# Temp.net
KiCad netlist of a schematic drawn in EAGLE
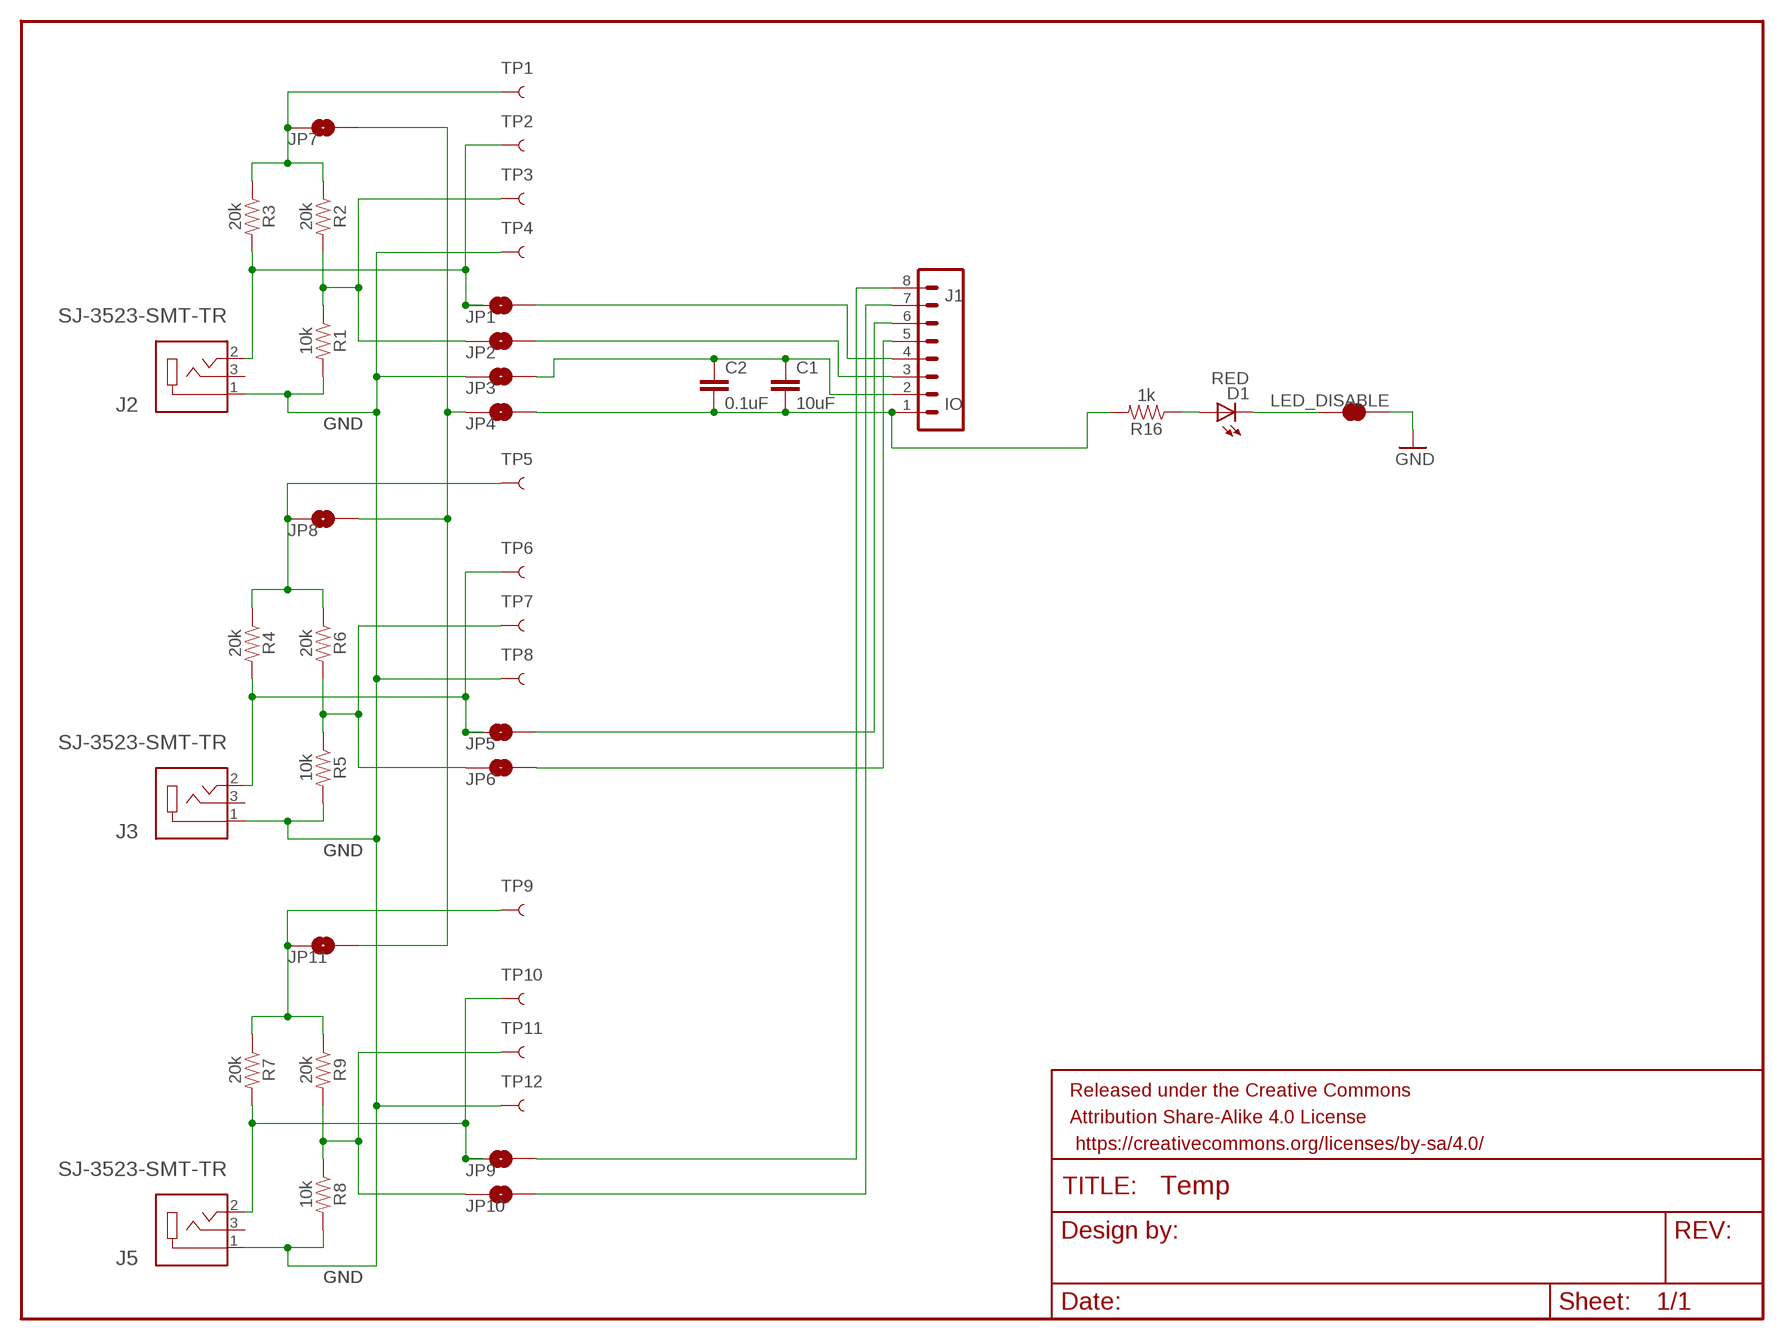
[diagram p0: schematic, sheet 1]

(export (version "E")
  (design (tool "Eeschema 10.0.6"))
  (components
    (comp (ref "C1")
      (value "10uF")
      (footprint "eagle-import:0603")
      (libsource (lib "eagle-import") (part "10UF-0603-6.3V-20%"))
    )
    (comp (ref "C2")
      (value "0.1uF")
      (footprint "eagle-import:0603")
      (libsource (lib "eagle-import") (part "0.1UF-0603-25V-(+80/-20%)"))
    )
    (comp (ref "D1")
      (value "RED")
      (footprint "eagle-import:LED-0603")
      (libsource (lib "eagle-import") (part "LED-RED0603"))
    )
    (comp (ref "FRAME1")
      (value "FRAME-LETTERNO_PACKAGE")
      (footprint "eagle-import:DUMMY")
      (fields (field (name "DESIGNER") "Nobody"))
      (libsource (lib "eagle-import") (part "FRAME-LETTERNO_PACKAGE"))
    )
    (comp (ref "J1")
      (value "IO")
      (footprint "eagle-import:1X08")
      (libsource (lib "eagle-import") (part "CONN_08{dblquote}"))
    )
    (comp (ref "J2")
      (value "SJ-3523-SMT-TR")
      (footprint "eagle-import:CUI_SJ-3523-SMT-TR")
      (fields (field (name "MF") "CUI Devices"))
      (libsource (lib "eagle-import") (part "SJ-3523-SMT-TR"))
    )
    (comp (ref "J3")
      (value "SJ-3523-SMT-TR")
      (footprint "eagle-import:CUI_SJ-3523-SMT-TR")
      (fields (field (name "MF") "CUI Devices"))
      (libsource (lib "eagle-import") (part "SJ-3523-SMT-TR"))
    )
    (comp (ref "J5")
      (value "SJ-3523-SMT-TR")
      (footprint "eagle-import:CUI_SJ-3523-SMT-TR")
      (fields (field (name "MF") "CUI Devices"))
      (libsource (lib "eagle-import") (part "SJ-3523-SMT-TR"))
    )
    (comp (ref "JP1")
      (value "JUMPER-SMT_2_NO_NO-SILK")
      (footprint "eagle-import:SMT-JUMPER_2_NO_NO-SILK")
      (libsource (lib "eagle-import") (part "JUMPER-SMT_2_NO_NO-SILK"))
    )
    (comp (ref "JP2")
      (value "JUMPER-SMT_2_NO_NO-SILK")
      (footprint "eagle-import:SMT-JUMPER_2_NO_NO-SILK")
      (libsource (lib "eagle-import") (part "JUMPER-SMT_2_NO_NO-SILK"))
    )
    (comp (ref "JP3")
      (value "JUMPER-SMT_2_NO_NO-SILK")
      (footprint "eagle-import:SMT-JUMPER_2_NO_NO-SILK")
      (libsource (lib "eagle-import") (part "JUMPER-SMT_2_NO_NO-SILK"))
    )
    (comp (ref "JP4")
      (value "JUMPER-SMT_2_NO_NO-SILK")
      (footprint "eagle-import:SMT-JUMPER_2_NO_NO-SILK")
      (libsource (lib "eagle-import") (part "JUMPER-SMT_2_NO_NO-SILK"))
    )
    (comp (ref "JP5")
      (value "JUMPER-SMT_2_NO_NO-SILK")
      (footprint "eagle-import:SMT-JUMPER_2_NO_NO-SILK")
      (libsource (lib "eagle-import") (part "JUMPER-SMT_2_NO_NO-SILK"))
    )
    (comp (ref "JP6")
      (value "JUMPER-SMT_2_NO_NO-SILK")
      (footprint "eagle-import:SMT-JUMPER_2_NO_NO-SILK")
      (libsource (lib "eagle-import") (part "JUMPER-SMT_2_NO_NO-SILK"))
    )
    (comp (ref "JP7")
      (value "JUMPER-SMT_2_NO_NO-SILK")
      (footprint "eagle-import:SMT-JUMPER_2_NO_NO-SILK")
      (libsource (lib "eagle-import") (part "JUMPER-SMT_2_NO_NO-SILK"))
    )
    (comp (ref "JP8")
      (value "JUMPER-SMT_2_NO_NO-SILK")
      (footprint "eagle-import:SMT-JUMPER_2_NO_NO-SILK")
      (libsource (lib "eagle-import") (part "JUMPER-SMT_2_NO_NO-SILK"))
    )
    (comp (ref "JP9")
      (value "JUMPER-SMT_2_NO_NO-SILK")
      (footprint "eagle-import:SMT-JUMPER_2_NO_NO-SILK")
      (libsource (lib "eagle-import") (part "JUMPER-SMT_2_NO_NO-SILK"))
    )
    (comp (ref "JP10")
      (value "JUMPER-SMT_2_NO_NO-SILK")
      (footprint "eagle-import:SMT-JUMPER_2_NO_NO-SILK")
      (libsource (lib "eagle-import") (part "JUMPER-SMT_2_NO_NO-SILK"))
    )
    (comp (ref "JP11")
      (value "JUMPER-SMT_2_NO_NO-SILK")
      (footprint "eagle-import:SMT-JUMPER_2_NO_NO-SILK")
      (libsource (lib "eagle-import") (part "JUMPER-SMT_2_NO_NO-SILK"))
    )
    (comp (ref "LED_DISABLE")
      (value "JUMPER-SMT_2_NC_TRACE_SILK")
      (footprint "eagle-import:SMT-JUMPER_2_NC_TRACE_SILK")
      (libsource (lib "eagle-import") (part "JUMPER-SMT_2_NC_TRACE_SILK"))
    )
    (comp (ref "R1")
      (value "10k")
      (footprint "eagle-import:0603")
      (libsource (lib "eagle-import") (part "10KOHM-0603-1/10W-1%"))
    )
    (comp (ref "R2")
      (value "20k")
      (footprint "eagle-import:0603")
      (libsource (lib "eagle-import") (part "20KOHM-0603-1/10W-1%"))
    )
    (comp (ref "R3")
      (value "20k")
      (footprint "eagle-import:0603")
      (libsource (lib "eagle-import") (part "20KOHM-0603-1/10W-1%"))
    )
    (comp (ref "R4")
      (value "20k")
      (footprint "eagle-import:0603")
      (libsource (lib "eagle-import") (part "20KOHM-0603-1/10W-1%"))
    )
    (comp (ref "R5")
      (value "10k")
      (footprint "eagle-import:0603")
      (libsource (lib "eagle-import") (part "10KOHM-0603-1/10W-1%"))
    )
    (comp (ref "R6")
      (value "20k")
      (footprint "eagle-import:0603")
      (libsource (lib "eagle-import") (part "20KOHM-0603-1/10W-1%"))
    )
    (comp (ref "R7")
      (value "20k")
      (footprint "eagle-import:0603")
      (libsource (lib "eagle-import") (part "20KOHM-0603-1/10W-1%"))
    )
    (comp (ref "R8")
      (value "10k")
      (footprint "eagle-import:0603")
      (libsource (lib "eagle-import") (part "10KOHM-0603-1/10W-1%"))
    )
    (comp (ref "R9")
      (value "20k")
      (footprint "eagle-import:0603")
      (libsource (lib "eagle-import") (part "20KOHM-0603-1/10W-1%"))
    )
    (comp (ref "R16")
      (value "1k")
      (footprint "eagle-import:0603")
      (libsource (lib "eagle-import") (part "1KOHM-0603-1/10W-1%"))
    )
    (comp (ref "TP1")
      (value "TEST-POINT3X5")
      (footprint "eagle-import:PAD.03X.05")
      (libsource (lib "eagle-import") (part "TEST-POINT3X5"))
    )
    (comp (ref "TP2")
      (value "TEST-POINT3X5")
      (footprint "eagle-import:PAD.03X.05")
      (libsource (lib "eagle-import") (part "TEST-POINT3X5"))
    )
    (comp (ref "TP3")
      (value "TEST-POINT3X5")
      (footprint "eagle-import:PAD.03X.05")
      (libsource (lib "eagle-import") (part "TEST-POINT3X5"))
    )
    (comp (ref "TP4")
      (value "TEST-POINT3X5")
      (footprint "eagle-import:PAD.03X.05")
      (libsource (lib "eagle-import") (part "TEST-POINT3X5"))
    )
    (comp (ref "TP5")
      (value "TEST-POINT3X5")
      (footprint "eagle-import:PAD.03X.05")
      (libsource (lib "eagle-import") (part "TEST-POINT3X5"))
    )
    (comp (ref "TP6")
      (value "TEST-POINT3X5")
      (footprint "eagle-import:PAD.03X.05")
      (libsource (lib "eagle-import") (part "TEST-POINT3X5"))
    )
    (comp (ref "TP7")
      (value "TEST-POINT3X5")
      (footprint "eagle-import:PAD.03X.05")
      (libsource (lib "eagle-import") (part "TEST-POINT3X5"))
    )
    (comp (ref "TP8")
      (value "TEST-POINT3X5")
      (footprint "eagle-import:PAD.03X.05")
      (libsource (lib "eagle-import") (part "TEST-POINT3X5"))
    )
    (comp (ref "TP9")
      (value "TEST-POINT3X5")
      (footprint "eagle-import:PAD.03X.05")
      (libsource (lib "eagle-import") (part "TEST-POINT3X5"))
    )
    (comp (ref "TP10")
      (value "TEST-POINT3X5")
      (footprint "eagle-import:PAD.03X.05")
      (libsource (lib "eagle-import") (part "TEST-POINT3X5"))
    )
    (comp (ref "TP11")
      (value "TEST-POINT3X5")
      (footprint "eagle-import:PAD.03X.05")
      (libsource (lib "eagle-import") (part "TEST-POINT3X5"))
    )
    (comp (ref "TP12")
      (value "TEST-POINT3X5")
      (footprint "eagle-import:PAD.03X.05")
      (libsource (lib "eagle-import") (part "TEST-POINT3X5"))
    )
  )
  (nets
    (net (code "1") (name "GND") (class "Default")
      (node (ref "J2") (pin "1") (pinfunction "1_1") (pintype "passive"))
      (node (ref "J3") (pin "1") (pinfunction "1_1") (pintype "passive"))
      (node (ref "J5") (pin "1") (pinfunction "1_1") (pintype "passive"))
      (node (ref "JP3") (pin "1") (pinfunction "1_1") (pintype "passive"))
      (node (ref "LED_DISABLE") (pin "1") (pinfunction "1_1") (pintype "passive"))
      (node (ref "R1") (pin "2") (pinfunction "2_2") (pintype "passive"))
      (node (ref "R5") (pin "2") (pinfunction "2_2") (pintype "passive"))
      (node (ref "R8") (pin "2") (pinfunction "2_2") (pintype "passive"))
      (node (ref "TP12") (pin "P$1") (pinfunction "1_P$1") (pintype "bidirectional"))
      (node (ref "TP4") (pin "P$1") (pinfunction "1_P$1") (pintype "bidirectional"))
      (node (ref "TP8") (pin "P$1") (pinfunction "1_P$1") (pintype "bidirectional"))
    )
    (net (code "2") (name "Net-(C1-Pad1)") (class "Default")
      (node (ref "C1") (pin "1") (pinfunction "1_1") (pintype "passive"))
      (node (ref "C2") (pin "1") (pinfunction "1_1") (pintype "passive"))
      (node (ref "J1") (pin "2") (pinfunction "2_2") (pintype "passive"))
      (node (ref "JP3") (pin "2") (pinfunction "2_2") (pintype "passive"))
    )
    (net (code "3") (name "Net-(C1-Pad2)") (class "Default")
      (node (ref "C1") (pin "2") (pinfunction "2_2") (pintype "passive"))
      (node (ref "C2") (pin "2") (pinfunction "2_2") (pintype "passive"))
      (node (ref "J1") (pin "1") (pinfunction "1_1") (pintype "passive"))
      (node (ref "JP4") (pin "2") (pinfunction "2_2") (pintype "passive"))
      (node (ref "R16") (pin "2") (pinfunction "2_2") (pintype "passive"))
    )
    (net (code "4") (name "Net-(D1-PadA)") (class "Default")
      (node (ref "D1") (pin "A") (pinfunction "A_A") (pintype "passive"))
      (node (ref "R16") (pin "1") (pinfunction "1_1") (pintype "passive"))
    )
    (net (code "5") (name "Net-(D1-PadC)") (class "Default")
      (node (ref "D1") (pin "C") (pinfunction "C_C") (pintype "passive"))
      (node (ref "LED_DISABLE") (pin "2") (pinfunction "2_2") (pintype "passive"))
    )
    (net (code "6") (name "Net-(J1-Pad3)") (class "Default")
      (node (ref "J1") (pin "3") (pinfunction "3_3") (pintype "passive"))
      (node (ref "JP2") (pin "2") (pinfunction "2_2") (pintype "passive"))
    )
    (net (code "7") (name "Net-(J1-Pad4)") (class "Default")
      (node (ref "J1") (pin "4") (pinfunction "4_4") (pintype "passive"))
      (node (ref "JP1") (pin "2") (pinfunction "2_2") (pintype "passive"))
    )
    (net (code "8") (name "Net-(J1-Pad5)") (class "Default")
      (node (ref "J1") (pin "5") (pinfunction "5_5") (pintype "passive"))
      (node (ref "JP6") (pin "2") (pinfunction "2_2") (pintype "passive"))
    )
    (net (code "9") (name "Net-(J1-Pad6)") (class "Default")
      (node (ref "J1") (pin "6") (pinfunction "6_6") (pintype "passive"))
      (node (ref "JP5") (pin "2") (pinfunction "2_2") (pintype "passive"))
    )
    (net (code "10") (name "Net-(J1-Pad7)") (class "Default")
      (node (ref "J1") (pin "7") (pinfunction "7_7") (pintype "passive"))
      (node (ref "JP10") (pin "2") (pinfunction "2_2") (pintype "passive"))
    )
    (net (code "11") (name "Net-(J1-Pad8)") (class "Default")
      (node (ref "J1") (pin "8") (pinfunction "8_8") (pintype "passive"))
      (node (ref "JP9") (pin "2") (pinfunction "2_2") (pintype "passive"))
    )
    (net (code "12") (name "Net-(JP11-Pad2)") (class "Default")
      (node (ref "JP11") (pin "2") (pinfunction "2_2") (pintype "passive"))
      (node (ref "JP4") (pin "1") (pinfunction "1_1") (pintype "passive"))
      (node (ref "JP7") (pin "2") (pinfunction "2_2") (pintype "passive"))
      (node (ref "JP8") (pin "2") (pinfunction "2_2") (pintype "passive"))
    )
    (net (code "13") (name "Net-(TP1-1)") (class "Default")
      (node (ref "JP7") (pin "1") (pinfunction "1_1") (pintype "passive"))
      (node (ref "R2") (pin "1") (pinfunction "1_1") (pintype "passive"))
      (node (ref "R3") (pin "1") (pinfunction "1_1") (pintype "passive"))
      (node (ref "TP1") (pin "P$1") (pinfunction "1_P$1") (pintype "bidirectional"))
    )
    (net (code "14") (name "Net-(TP2-1)") (class "Default")
      (node (ref "J2") (pin "2") (pinfunction "2_2") (pintype "passive"))
      (node (ref "JP1") (pin "1") (pinfunction "1_1") (pintype "passive"))
      (node (ref "R3") (pin "2") (pinfunction "2_2") (pintype "passive"))
      (node (ref "TP2") (pin "P$1") (pinfunction "1_P$1") (pintype "bidirectional"))
    )
    (net (code "15") (name "Net-(TP3-1)") (class "Default")
      (node (ref "JP2") (pin "1") (pinfunction "1_1") (pintype "passive"))
      (node (ref "R1") (pin "1") (pinfunction "1_1") (pintype "passive"))
      (node (ref "R2") (pin "2") (pinfunction "2_2") (pintype "passive"))
      (node (ref "TP3") (pin "P$1") (pinfunction "1_P$1") (pintype "bidirectional"))
    )
    (net (code "16") (name "Net-(TP5-1)") (class "Default")
      (node (ref "JP8") (pin "1") (pinfunction "1_1") (pintype "passive"))
      (node (ref "R4") (pin "1") (pinfunction "1_1") (pintype "passive"))
      (node (ref "R6") (pin "1") (pinfunction "1_1") (pintype "passive"))
      (node (ref "TP5") (pin "P$1") (pinfunction "1_P$1") (pintype "bidirectional"))
    )
    (net (code "17") (name "Net-(TP6-1)") (class "Default")
      (node (ref "J3") (pin "2") (pinfunction "2_2") (pintype "passive"))
      (node (ref "JP5") (pin "1") (pinfunction "1_1") (pintype "passive"))
      (node (ref "R4") (pin "2") (pinfunction "2_2") (pintype "passive"))
      (node (ref "TP6") (pin "P$1") (pinfunction "1_P$1") (pintype "bidirectional"))
    )
    (net (code "18") (name "Net-(TP7-1)") (class "Default")
      (node (ref "JP6") (pin "1") (pinfunction "1_1") (pintype "passive"))
      (node (ref "R5") (pin "1") (pinfunction "1_1") (pintype "passive"))
      (node (ref "R6") (pin "2") (pinfunction "2_2") (pintype "passive"))
      (node (ref "TP7") (pin "P$1") (pinfunction "1_P$1") (pintype "bidirectional"))
    )
    (net (code "19") (name "Net-(TP9-1)") (class "Default")
      (node (ref "JP11") (pin "1") (pinfunction "1_1") (pintype "passive"))
      (node (ref "R7") (pin "1") (pinfunction "1_1") (pintype "passive"))
      (node (ref "R9") (pin "1") (pinfunction "1_1") (pintype "passive"))
      (node (ref "TP9") (pin "P$1") (pinfunction "1_P$1") (pintype "bidirectional"))
    )
    (net (code "20") (name "Net-(TP10-1)") (class "Default")
      (node (ref "J5") (pin "2") (pinfunction "2_2") (pintype "passive"))
      (node (ref "JP9") (pin "1") (pinfunction "1_1") (pintype "passive"))
      (node (ref "R7") (pin "2") (pinfunction "2_2") (pintype "passive"))
      (node (ref "TP10") (pin "P$1") (pinfunction "1_P$1") (pintype "bidirectional"))
    )
    (net (code "21") (name "Net-(TP11-1)") (class "Default")
      (node (ref "JP10") (pin "1") (pinfunction "1_1") (pintype "passive"))
      (node (ref "R8") (pin "1") (pinfunction "1_1") (pintype "passive"))
      (node (ref "R9") (pin "2") (pinfunction "2_2") (pintype "passive"))
      (node (ref "TP11") (pin "P$1") (pinfunction "1_P$1") (pintype "bidirectional"))
    )
    (net (code "22") (name "unconnected-(J2-Pad3)") (class "Default")
      (node (ref "J2") (pin "3") (pinfunction "3_3") (pintype "passive"))
    )
    (net (code "23") (name "unconnected-(J3-Pad3)") (class "Default")
      (node (ref "J3") (pin "3") (pinfunction "3_3") (pintype "passive"))
    )
    (net (code "24") (name "unconnected-(J5-Pad3)") (class "Default")
      (node (ref "J5") (pin "3") (pinfunction "3_3") (pintype "passive"))
    )
  )
)
